# IPMC_V71V01.net
KiCad netlist of a schematic drawn in Altium Designer
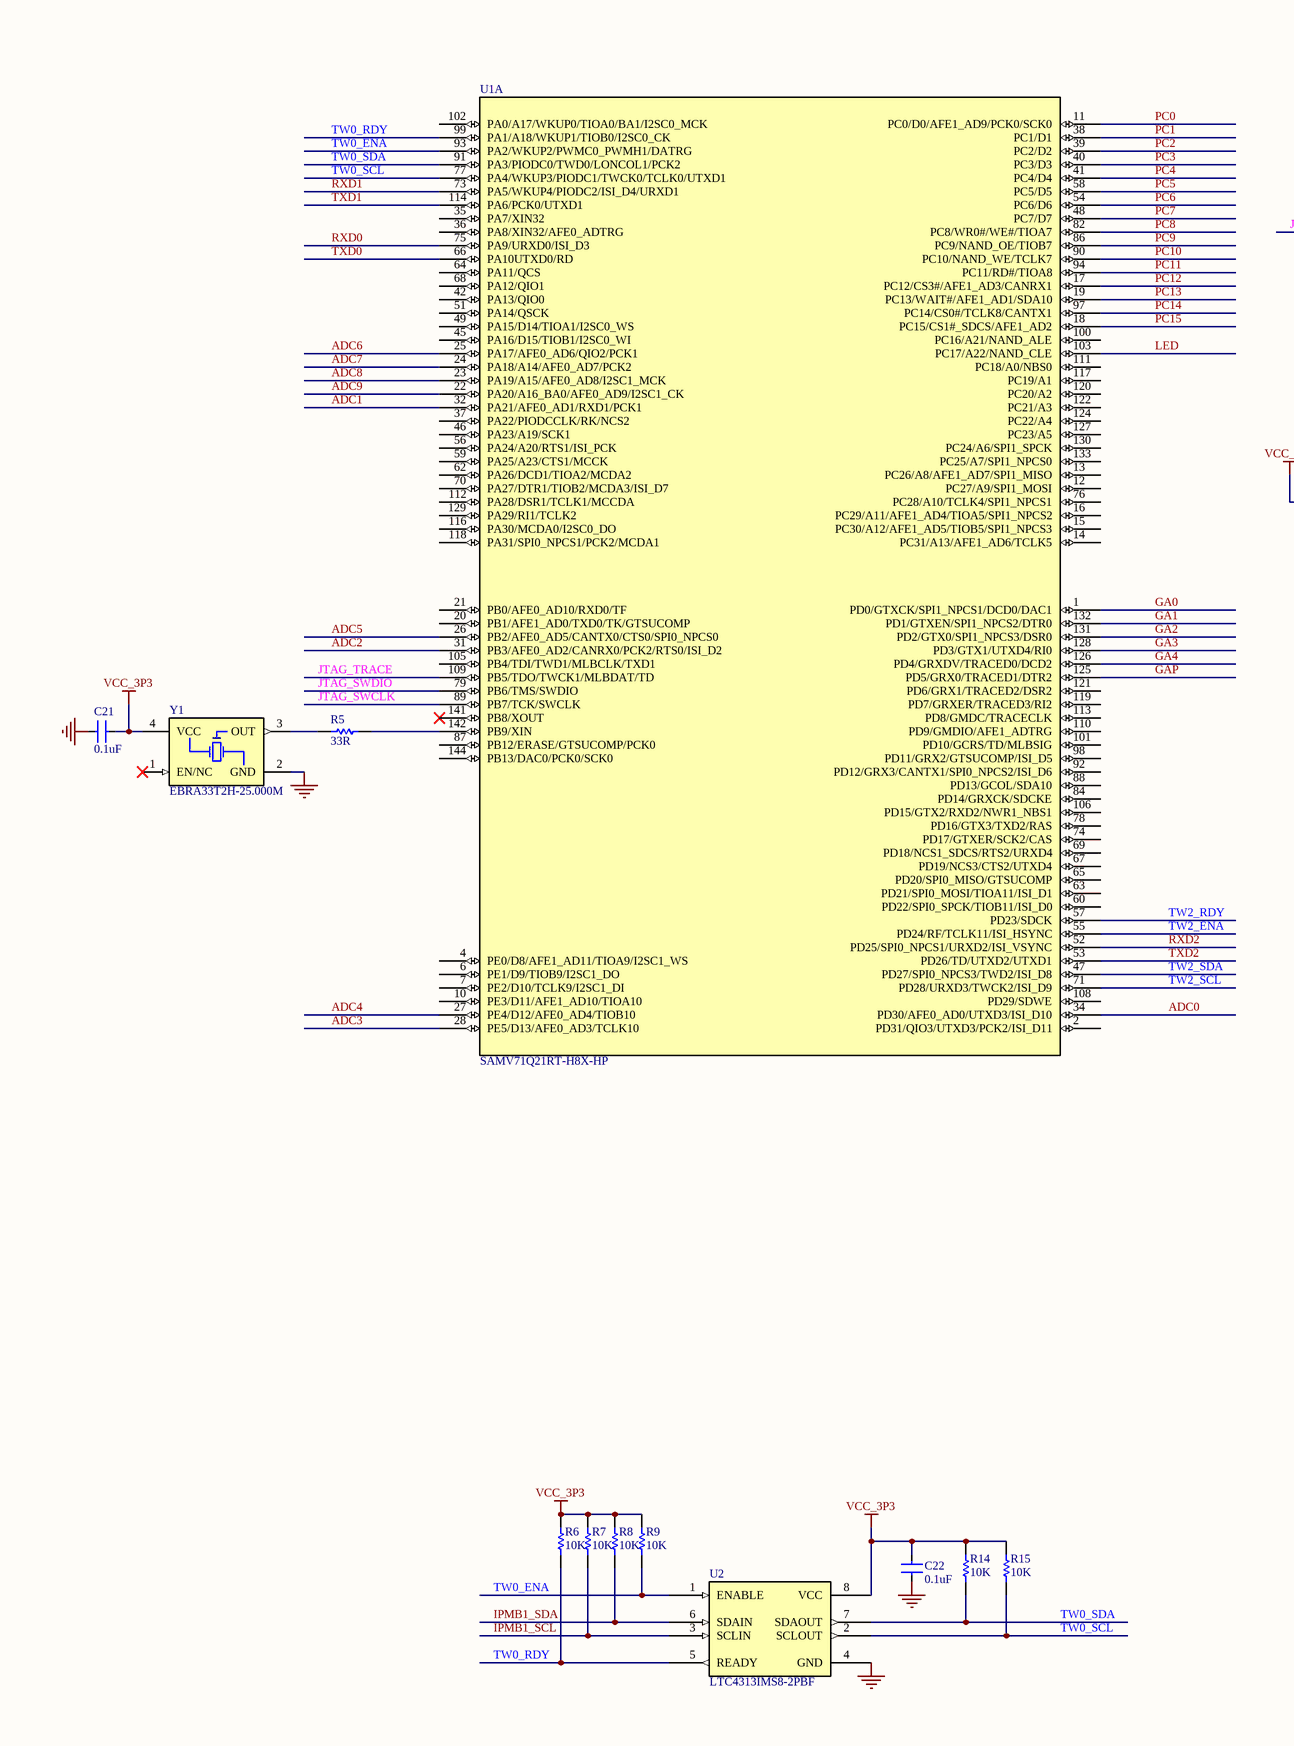
[diagram p0: IPMC_V71V01.SchDoc, left]
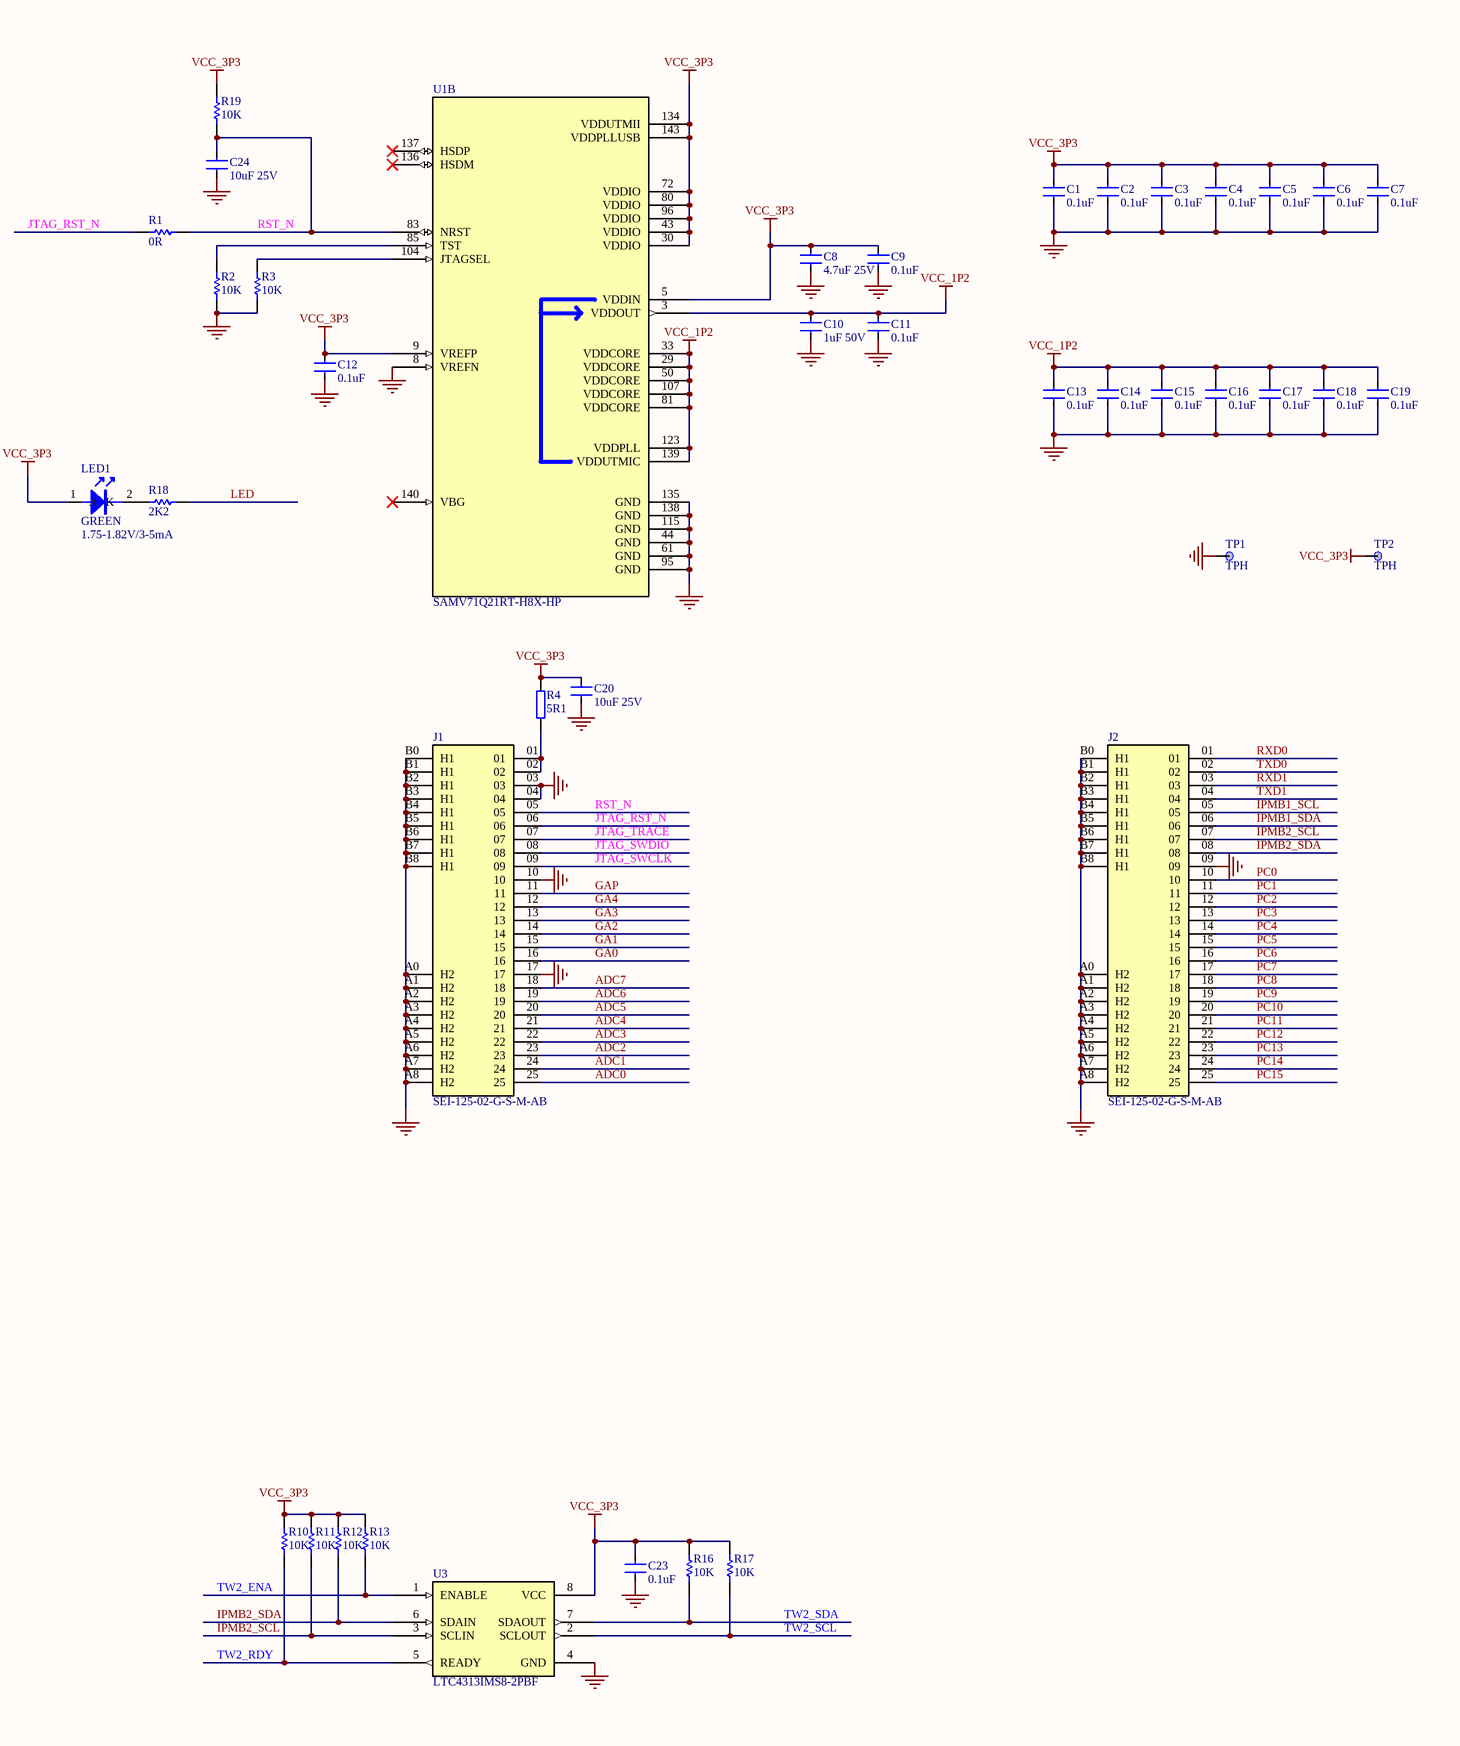
[diagram p1: IPMC_V71V01.SchDoc, right]

(export (version "E")
  (design (tool "Eeschema 10.0.6"))
  (components
    (comp (ref "C1")
      (value "0.1uF")
      (footprint "0603C")
      (description "X8L AEC-Q200")
      (fields (field (name "MANUFACTURER") "muRata") (field (name "PARTNUMBER") "GCJ188L8EL104KA07"))
      (libsource (lib "AD20_RCX") (part "CAP-0.1u-100v-0603"))
    )
    (comp (ref "C2")
      (value "0.1uF")
      (footprint "0603C")
      (description "X8L AEC-Q200")
      (fields (field (name "MANUFACTURER") "muRata") (field (name "PARTNUMBER") "GCJ188L8EL104KA07"))
      (libsource (lib "AD20_RCX") (part "CAP-0.1u-100v-0603"))
    )
    (comp (ref "C3")
      (value "0.1uF")
      (footprint "0603C")
      (description "X8L AEC-Q200")
      (fields (field (name "MANUFACTURER") "muRata") (field (name "PARTNUMBER") "GCJ188L8EL104KA07"))
      (libsource (lib "AD20_RCX") (part "CAP-0.1u-100v-0603"))
    )
    (comp (ref "C4")
      (value "0.1uF")
      (footprint "0603C")
      (description "X8L AEC-Q200")
      (fields (field (name "MANUFACTURER") "muRata") (field (name "PARTNUMBER") "GCJ188L8EL104KA07"))
      (libsource (lib "AD20_RCX") (part "CAP-0.1u-100v-0603"))
    )
    (comp (ref "C5")
      (value "0.1uF")
      (footprint "0603C")
      (description "X8L AEC-Q200")
      (fields (field (name "MANUFACTURER") "muRata") (field (name "PARTNUMBER") "GCJ188L8EL104KA07"))
      (libsource (lib "AD20_RCX") (part "CAP-0.1u-100v-0603"))
    )
    (comp (ref "C6")
      (value "0.1uF")
      (footprint "0603C")
      (description "X8L AEC-Q200")
      (fields (field (name "MANUFACTURER") "muRata") (field (name "PARTNUMBER") "GCJ188L8EL104KA07"))
      (libsource (lib "AD20_RCX") (part "CAP-0.1u-100v-0603"))
    )
    (comp (ref "C7")
      (value "0.1uF")
      (footprint "0603C")
      (description "X8L AEC-Q200")
      (fields (field (name "MANUFACTURER") "muRata") (field (name "PARTNUMBER") "GCJ188L8EL104KA07"))
      (libsource (lib "AD20_RCX") (part "CAP-0.1u-100v-0603"))
    )
    (comp (ref "C8")
      (value "4.7uF 25V")
      (footprint "0603C")
      (description "X5R AEC-Q200")
      (fields (field (name "PARTNUMBER") "GRT188R61E475KE13") (field (name "MANUFACTURER") "muRata"))
      (libsource (lib "AD20_RCX") (part "CAP-4.7u-25v-0603"))
    )
    (comp (ref "C9")
      (value "0.1uF")
      (footprint "0603C")
      (description "X8L AEC-Q200")
      (fields (field (name "MANUFACTURER") "muRata") (field (name "PARTNUMBER") "GCJ188L8EL104KA07"))
      (libsource (lib "AD20_RCX") (part "CAP-0.1u-100v-0603"))
    )
    (comp (ref "C10")
      (value "1uF 50V")
      (footprint "0603C")
      (description "X5R AEC-Q200")
      (fields (field (name "PARTNUMBER") "GRT188R61H105KE13") (field (name "MANUFACTURER") "muRata"))
      (libsource (lib "AD20_RCX") (part "CAP-1u-50v-0603"))
    )
    (comp (ref "C11")
      (value "0.1uF")
      (footprint "0603C")
      (description "X8L AEC-Q200")
      (fields (field (name "MANUFACTURER") "muRata") (field (name "PARTNUMBER") "GCJ188L8EL104KA07"))
      (libsource (lib "AD20_RCX") (part "CAP-0.1u-100v-0603"))
    )
    (comp (ref "C12")
      (value "0.1uF")
      (footprint "0603C")
      (description "X8L AEC-Q200")
      (fields (field (name "MANUFACTURER") "muRata") (field (name "PARTNUMBER") "GCJ188L8EL104KA07"))
      (libsource (lib "AD20_RCX") (part "CAP-0.1u-100v-0603"))
    )
    (comp (ref "C13")
      (value "0.1uF")
      (footprint "0603C")
      (description "X8L AEC-Q200")
      (fields (field (name "MANUFACTURER") "muRata") (field (name "PARTNUMBER") "GCJ188L8EL104KA07"))
      (libsource (lib "AD20_RCX") (part "CAP-0.1u-100v-0603"))
    )
    (comp (ref "C14")
      (value "0.1uF")
      (footprint "0603C")
      (description "X8L AEC-Q200")
      (fields (field (name "MANUFACTURER") "muRata") (field (name "PARTNUMBER") "GCJ188L8EL104KA07"))
      (libsource (lib "AD20_RCX") (part "CAP-0.1u-100v-0603"))
    )
    (comp (ref "C15")
      (value "0.1uF")
      (footprint "0603C")
      (description "X8L AEC-Q200")
      (fields (field (name "MANUFACTURER") "muRata") (field (name "PARTNUMBER") "GCJ188L8EL104KA07"))
      (libsource (lib "AD20_RCX") (part "CAP-0.1u-100v-0603"))
    )
    (comp (ref "C16")
      (value "0.1uF")
      (footprint "0603C")
      (description "X8L AEC-Q200")
      (fields (field (name "MANUFACTURER") "muRata") (field (name "PARTNUMBER") "GCJ188L8EL104KA07"))
      (libsource (lib "AD20_RCX") (part "CAP-0.1u-100v-0603"))
    )
    (comp (ref "C17")
      (value "0.1uF")
      (footprint "0603C")
      (description "X8L AEC-Q200")
      (fields (field (name "MANUFACTURER") "muRata") (field (name "PARTNUMBER") "GCJ188L8EL104KA07"))
      (libsource (lib "AD20_RCX") (part "CAP-0.1u-100v-0603"))
    )
    (comp (ref "C18")
      (value "0.1uF")
      (footprint "0603C")
      (description "X8L AEC-Q200")
      (fields (field (name "MANUFACTURER") "muRata") (field (name "PARTNUMBER") "GCJ188L8EL104KA07"))
      (libsource (lib "AD20_RCX") (part "CAP-0.1u-100v-0603"))
    )
    (comp (ref "C19")
      (value "0.1uF")
      (footprint "0603C")
      (description "X8L AEC-Q200")
      (fields (field (name "MANUFACTURER") "muRata") (field (name "PARTNUMBER") "GCJ188L8EL104KA07"))
      (libsource (lib "AD20_RCX") (part "CAP-0.1u-100v-0603"))
    )
    (comp (ref "C20")
      (value "10uF 25V")
      (footprint "0603C")
      (description "X5R AEC-Q200")
      (fields (field (name "PARTNUMBER") "GRT188R61E106ME13") (field (name "MANUFACTURER") "muRata"))
      (libsource (lib "AD20_RCX") (part "CAP-10u-25v-0603"))
    )
    (comp (ref "C21")
      (value "0.1uF")
      (footprint "0603C")
      (description "X7R AEC-Q200")
      (fields (field (name "PARTNUMBER") "GCJ188R71H104KA12") (field (name "MANUFACTURER") "muRata"))
      (libsource (lib "AD") (part "CAP-0.1u-50v-0603"))
    )
    (comp (ref "C22")
      (value "0.1uF")
      (footprint "0603C")
      (description "X7R AEC-Q200")
      (fields (field (name "PARTNUMBER") "GCJ188R71H104KA12") (field (name "MANUFACTURER") "muRata"))
      (libsource (lib "AD") (part "CAP-0.1u-50v-0603"))
    )
    (comp (ref "C23")
      (value "0.1uF")
      (footprint "0603C")
      (description "X7R AEC-Q200")
      (fields (field (name "PARTNUMBER") "GCJ188R71H104KA12") (field (name "MANUFACTURER") "muRata"))
      (libsource (lib "AD") (part "CAP-0.1u-50v-0603"))
    )
    (comp (ref "C24")
      (value "10uF 25V")
      (footprint "0603C")
      (description "X5R AEC-Q200")
      (fields (field (name "PARTNUMBER") "GRT188R61E106ME13") (field (name "MANUFACTURER") "muRata"))
      (libsource (lib "AD20_RCX") (part "CAP-10u-25v-0603"))
    )
    (comp (ref "J1")
      (value "SEI-125-02-G-S-M-AB")
      (footprint "SAMTEC_SEI-125-02-G-S-M-AB_IPMC")
      (description "25 Position Spring Compression Contact, Non-Gendered Connector Surface Mount")
      (fields (field (name "MF") "Samtec") (field (name "MP") "SEI-125-02-G-S-E-AB"))
      (libsource (lib "ChMC_V71V01_PCB_Project") (part "SEI-125-02-G-S-E-AB"))
    )
    (comp (ref "J2")
      (value "SEI-125-02-G-S-M-AB")
      (footprint "SAMTEC_SEI-125-02-G-S-M-AB_IPMC")
      (description "25 Position Spring Compression Contact, Non-Gendered Connector Surface Mount")
      (fields (field (name "MF") "Samtec") (field (name "MP") "SEI-125-02-G-S-E-AB"))
      (libsource (lib "ChMC_V71V01_PCB_Project") (part "SEI-125-02-G-S-E-AB"))
    )
    (comp (ref "LED1")
      (value "GREEN")
      (footprint "0603LED")
      (description "1.75-1.82V/3-5mA")
      (fields (field (name "PARAMETER 1") "1.75-1.82V/3-5mA"))
      (libsource (lib "AD20_RCX") (part "D-LED0603-GREEN"))
    )
    (comp (ref "R1")
      (value "0R")
      (footprint "0603R")
      (description "1%/0603")
      (fields (field (name "PARTNUMBER") "AC0603FR-070RL") (field (name "MANUFACTURER") "YAGEO"))
      (libsource (lib "AD20_RCX") (part "Res1-0R"))
    )
    (comp (ref "R2")
      (value "10K")
      (footprint "0603R")
      (description "1%/0603")
      (fields (field (name "PARTNUMBER") "AC0603FR-0710KL") (field (name "MANUFACTURER") "YAGEO"))
      (libsource (lib "AD20_RCX") (part "Res1-10K"))
    )
    (comp (ref "R3")
      (value "10K")
      (footprint "0603R")
      (description "1%/0603")
      (fields (field (name "PARTNUMBER") "AC0603FR-0710KL") (field (name "MANUFACTURER") "YAGEO"))
      (libsource (lib "AD20_RCX") (part "Res1-10K"))
    )
    (comp (ref "R4")
      (value "5R1")
      (footprint "0805R")
      (description "1%/0805")
      (fields (field (name "PARTNUMBER") "AC0805FR-075R1L") (field (name "MANUFACTURER") "YAGEO"))
      (libsource (lib "AD20_RCX") (part "Res2-5R1-0805"))
    )
    (comp (ref "R5")
      (value "33R")
      (footprint "0603R")
      (description "1%/0603")
      (fields (field (name "PARTNUMBER") "AC0603FR-0733RL") (field (name "MANUFACTURER") "YAGEO"))
      (libsource (lib "AD20_RCX") (part "Res1-33R"))
    )
    (comp (ref "R6")
      (value "10K")
      (footprint "0603R")
      (description "1%/0603")
      (fields (field (name "PARTNUMBER") "AC0603FR-0710KL") (field (name "MANUFACTURER") "YAGEO"))
      (libsource (lib "AD20_RCX") (part "Res1-10K"))
    )
    (comp (ref "R7")
      (value "10K")
      (footprint "0603R")
      (description "1%/0603")
      (fields (field (name "PARTNUMBER") "AC0603FR-0710KL") (field (name "MANUFACTURER") "YAGEO"))
      (libsource (lib "AD20_RCX") (part "Res1-10K"))
    )
    (comp (ref "R8")
      (value "10K")
      (footprint "0603R")
      (description "1%/0603")
      (fields (field (name "PARTNUMBER") "AC0603FR-0710KL") (field (name "MANUFACTURER") "YAGEO"))
      (libsource (lib "AD20_RCX") (part "Res1-10K"))
    )
    (comp (ref "R9")
      (value "10K")
      (footprint "0603R")
      (description "1%/0603")
      (fields (field (name "PARTNUMBER") "AC0603FR-0710KL") (field (name "MANUFACTURER") "YAGEO"))
      (libsource (lib "AD20_RCX") (part "Res1-10K"))
    )
    (comp (ref "R10")
      (value "10K")
      (footprint "0603R")
      (description "1%/0603")
      (fields (field (name "PARTNUMBER") "AC0603FR-0710KL") (field (name "MANUFACTURER") "YAGEO"))
      (libsource (lib "AD20_RCX") (part "Res1-10K"))
    )
    (comp (ref "R11")
      (value "10K")
      (footprint "0603R")
      (description "1%/0603")
      (fields (field (name "PARTNUMBER") "AC0603FR-0710KL") (field (name "MANUFACTURER") "YAGEO"))
      (libsource (lib "AD20_RCX") (part "Res1-10K"))
    )
    (comp (ref "R12")
      (value "10K")
      (footprint "0603R")
      (description "1%/0603")
      (fields (field (name "PARTNUMBER") "AC0603FR-0710KL") (field (name "MANUFACTURER") "YAGEO"))
      (libsource (lib "AD20_RCX") (part "Res1-10K"))
    )
    (comp (ref "R13")
      (value "10K")
      (footprint "0603R")
      (description "1%/0603")
      (fields (field (name "PARTNUMBER") "AC0603FR-0710KL") (field (name "MANUFACTURER") "YAGEO"))
      (libsource (lib "AD20_RCX") (part "Res1-10K"))
    )
    (comp (ref "R14")
      (value "10K")
      (footprint "0603R")
      (description "1%/0603")
      (fields (field (name "PARTNUMBER") "AC0603FR-0710KL") (field (name "MANUFACTURER") "YAGEO"))
      (libsource (lib "IPMCv01_PCB_Project") (part "Res1-10K"))
    )
    (comp (ref "R15")
      (value "10K")
      (footprint "0603R")
      (description "1%/0603")
      (fields (field (name "PARTNUMBER") "AC0603FR-0710KL") (field (name "MANUFACTURER") "YAGEO"))
      (libsource (lib "IPMCv01_PCB_Project") (part "Res1-10K"))
    )
    (comp (ref "R16")
      (value "10K")
      (footprint "0603R")
      (description "1%/0603")
      (fields (field (name "PARTNUMBER") "AC0603FR-0710KL") (field (name "MANUFACTURER") "YAGEO"))
      (libsource (lib "IPMCv01_PCB_Project") (part "Res1-10K"))
    )
    (comp (ref "R17")
      (value "10K")
      (footprint "0603R")
      (description "1%/0603")
      (fields (field (name "PARTNUMBER") "AC0603FR-0710KL") (field (name "MANUFACTURER") "YAGEO"))
      (libsource (lib "IPMCv01_PCB_Project") (part "Res1-10K"))
    )
    (comp (ref "R18")
      (value "2K2")
      (footprint "0603R")
      (description "1%/0603")
      (fields (field (name "PARTNUMBER") "AC0603FR-072K2L") (field (name "MANUFACTURER") "YAGEO"))
      (libsource (lib "AD20_RCX") (part "Res1-2K2"))
    )
    (comp (ref "R19")
      (value "10K")
      (footprint "0603R")
      (description "1%/0603")
      (fields (field (name "PARTNUMBER") "AC0603FR-0710KL") (field (name "MANUFACTURER") "YAGEO"))
      (libsource (lib "AD20_RCX") (part "Res1-10K"))
    )
    (comp (ref "TP1") (value "TPH") (footprint "TP") (libsource (lib "AD20_CON") (part "TPH")))
    (comp (ref "TP2") (value "TPH") (footprint "TP") (libsource (lib "AD20_CON") (part "TPH")))
    (comp (ref "U1")
      (value "SAMV71Q21RT-H8X-HP")
      (footprint "LQFP144_2SB_MCH")
      (description "No Description Available")
      (libsource (lib "AD20_IC") (part "SAMV71Q21RT-H8X-HP"))
    )
    (comp (ref "U2")
      (value "LTC4313IMS8-2PBF")
      (footprint "MSOP-8_MS_LIT")
      (description "No Description Available")
      (libsource (lib "AD20_IC") (part "LTC4313IMS8-1PBF"))
    )
    (comp (ref "U3")
      (value "LTC4313IMS8-2PBF")
      (footprint "MSOP-8_MS_LIT")
      (description "No Description Available")
      (libsource (lib "AD20_IC") (part "LTC4313IMS8-1PBF"))
    )
    (comp (ref "Y1")
      (value "EBRA33T2H-25.000M")
      (footprint "50.000M 3P3 50PPM 10PF 3.2*5.0MM")
      (description "SPXO AEC-Q200")
      (fields (field (name "MANUFACTURER") "Ecliptec") (field (name "PARTNUMBER") "EBRA23T1H-50.000M"))
      (libsource (lib "AD20_RCX") (part "XTAL3_50M_SPXO_3.2_5.0"))
    )
  )
  (nets
    (net (code "1") (name "/ADC0") (class "Default")
      (node (ref "J1") (pin "25") (pinfunction "25_25") (pintype "passive"))
      (node (ref "U1") (pin "34") (pinfunction "PD30/UTXD3/ISI_D10_34") (pintype "bidirectional"))
    )
    (net (code "2") (name "/ADC1") (class "Default")
      (node (ref "J1") (pin "24") (pinfunction "24_24") (pintype "passive"))
      (node (ref "U1") (pin "32") (pinfunction "PA21/AFE0_AD1/RXD1/PCK1_32") (pintype "bidirectional"))
    )
    (net (code "3") (name "/ADC2") (class "Default")
      (node (ref "J1") (pin "23") (pinfunction "23_23") (pintype "passive"))
      (node (ref "U1") (pin "31") (pinfunction "PB3/AFE0_AD2/CANRX0/PCK2/RTS0/ISI_D2_31") (pintype "bidirectional"))
    )
    (net (code "4") (name "/ADC3") (class "Default")
      (node (ref "J1") (pin "22") (pinfunction "22_22") (pintype "passive"))
      (node (ref "U1") (pin "28") (pinfunction "PE5/D13/AFE0_AD3/TCLK10_28") (pintype "bidirectional"))
    )
    (net (code "5") (name "/ADC4") (class "Default")
      (node (ref "J1") (pin "21") (pinfunction "21_21") (pintype "passive"))
      (node (ref "U1") (pin "27") (pinfunction "PE4/D12/AFE0_AD4/TIOB10_27") (pintype "bidirectional"))
    )
    (net (code "6") (name "/ADC5") (class "Default")
      (node (ref "J1") (pin "20") (pinfunction "20_20") (pintype "passive"))
      (node (ref "U1") (pin "26") (pinfunction "PB2/AFE0_AD5/CANTX0/CTS0/SPI0_NPCS0_26") (pintype "bidirectional"))
    )
    (net (code "7") (name "/ADC6") (class "Default")
      (node (ref "J1") (pin "19") (pinfunction "19_19") (pintype "passive"))
      (node (ref "U1") (pin "25") (pinfunction "PA17/AFE0_AD6/QIO2/PCK1_25") (pintype "bidirectional"))
    )
    (net (code "8") (name "/ADC7") (class "Default")
      (node (ref "J1") (pin "18") (pinfunction "18_18") (pintype "passive"))
      (node (ref "U1") (pin "24") (pinfunction "PA18/A14/AFE0_AD7/PCK2_24") (pintype "bidirectional"))
    )
    (net (code "9") (name "/ADC8") (class "Default")
      (node (ref "U1") (pin "23") (pinfunction "PA19/A15/AFE0_AD8/I2SC1_MCK_23") (pintype "bidirectional"))
    )
    (net (code "10") (name "/ADC9") (class "Default")
      (node (ref "U1") (pin "22") (pinfunction "PA20/A16_BA0/AFE0_AD9/I2SC1_CK_22") (pintype "bidirectional"))
    )
    (net (code "11") (name "/GA0") (class "Default")
      (node (ref "J1") (pin "16") (pinfunction "16_16") (pintype "passive"))
      (node (ref "U1") (pin "1") (pinfunction "PD0/GTXCK/SPI1_NPCS1/DCD0/DAC1_1") (pintype "bidirectional"))
    )
    (net (code "12") (name "/GA1") (class "Default")
      (node (ref "J1") (pin "15") (pinfunction "15_15") (pintype "passive"))
      (node (ref "U1") (pin "132") (pinfunction "PD1/GTXEN/SPI1_NPCS2/DTR0_132") (pintype "bidirectional"))
    )
    (net (code "13") (name "/GA2") (class "Default")
      (node (ref "J1") (pin "14") (pinfunction "14_14") (pintype "passive"))
      (node (ref "U1") (pin "131") (pinfunction "PD2/GTX0/SPI1_NPCS3/DSR0_131") (pintype "bidirectional"))
    )
    (net (code "14") (name "/GA3") (class "Default")
      (node (ref "J1") (pin "13") (pinfunction "13_13") (pintype "passive"))
      (node (ref "U1") (pin "128") (pinfunction "PD3/GTX1/UTXD4/RI0_128") (pintype "bidirectional"))
    )
    (net (code "15") (name "/GA4") (class "Default")
      (node (ref "J1") (pin "12") (pinfunction "12_12") (pintype "passive"))
      (node (ref "U1") (pin "126") (pinfunction "PD4/GRXDV/TRACED0/DCD2_126") (pintype "bidirectional"))
    )
    (net (code "16") (name "/GAP") (class "Default")
      (node (ref "J1") (pin "11") (pinfunction "11_11") (pintype "passive"))
      (node (ref "U1") (pin "125") (pinfunction "PD5/GRX0/TRACED1/DTR2_125") (pintype "bidirectional"))
    )
    (net (code "17") (name "/IPMB1_SCL") (class "Default")
      (node (ref "J2") (pin "05") (pinfunction "05_05") (pintype "passive"))
      (node (ref "R7") (pin "1") (pinfunction "1_1") (pintype "passive"))
      (node (ref "U2") (pin "3") (pinfunction "SCLIN_3") (pintype "input"))
    )
    (net (code "18") (name "/IPMB1_SDA") (class "Default")
      (node (ref "J2") (pin "06") (pinfunction "06_06") (pintype "passive"))
      (node (ref "R8") (pin "1") (pinfunction "1_1") (pintype "passive"))
      (node (ref "U2") (pin "6") (pinfunction "SDAIN_6") (pintype "input"))
    )
    (net (code "19") (name "/IPMB2_SCL") (class "Default")
      (node (ref "J2") (pin "07") (pinfunction "07_07") (pintype "passive"))
      (node (ref "R11") (pin "1") (pinfunction "1_1") (pintype "passive"))
      (node (ref "U3") (pin "3") (pinfunction "SCLIN_3") (pintype "input"))
    )
    (net (code "20") (name "/IPMB2_SDA") (class "Default")
      (node (ref "J2") (pin "08") (pinfunction "08_08") (pintype "passive"))
      (node (ref "R12") (pin "1") (pinfunction "1_1") (pintype "passive"))
      (node (ref "U3") (pin "6") (pinfunction "SDAIN_6") (pintype "input"))
    )
    (net (code "21") (name "/JTAG_RST_N") (class "Default")
      (node (ref "J1") (pin "06") (pinfunction "06_06") (pintype "passive"))
      (node (ref "R1") (pin "1") (pinfunction "1_1") (pintype "passive"))
    )
    (net (code "22") (name "/JTAG_SWCLK") (class "Default")
      (node (ref "J1") (pin "09") (pinfunction "09_09") (pintype "passive"))
      (node (ref "U1") (pin "89") (pinfunction "PB7/TCK/SWCLK_89") (pintype "bidirectional"))
    )
    (net (code "23") (name "/JTAG_SWDIO") (class "Default")
      (node (ref "J1") (pin "08") (pinfunction "08_08") (pintype "passive"))
      (node (ref "U1") (pin "79") (pinfunction "PB6/TMS/SWDIO_79") (pintype "bidirectional"))
    )
    (net (code "24") (name "/JTAG_TRACE") (class "Default")
      (node (ref "J1") (pin "07") (pinfunction "07_07") (pintype "passive"))
      (node (ref "U1") (pin "109") (pinfunction "PB5/TDO/TWCK1/MLBDAT/TD_109") (pintype "bidirectional"))
    )
    (net (code "25") (name "/LED") (class "Default")
      (node (ref "R18") (pin "2") (pinfunction "2_2") (pintype "passive"))
      (node (ref "U1") (pin "103") (pinfunction "PC17/A22/NAND_CLE_103") (pintype "bidirectional"))
    )
    (net (code "26") (name "/PC0") (class "Default")
      (node (ref "J2") (pin "10") (pinfunction "10_10") (pintype "passive"))
      (node (ref "U1") (pin "11") (pinfunction "PC0/D0/AFE1_AD9/PCK0/SCK0_11") (pintype "bidirectional"))
    )
    (net (code "27") (name "/PC1") (class "Default")
      (node (ref "J2") (pin "11") (pinfunction "11_11") (pintype "passive"))
      (node (ref "U1") (pin "38") (pinfunction "PC1/D1_38") (pintype "bidirectional"))
    )
    (net (code "28") (name "/PC2") (class "Default")
      (node (ref "J2") (pin "12") (pinfunction "12_12") (pintype "passive"))
      (node (ref "U1") (pin "39") (pinfunction "PC2/D2_39") (pintype "bidirectional"))
    )
    (net (code "29") (name "/PC3") (class "Default")
      (node (ref "J2") (pin "13") (pinfunction "13_13") (pintype "passive"))
      (node (ref "U1") (pin "40") (pinfunction "PC3/D3_40") (pintype "bidirectional"))
    )
    (net (code "30") (name "/PC4") (class "Default")
      (node (ref "J2") (pin "14") (pinfunction "14_14") (pintype "passive"))
      (node (ref "U1") (pin "41") (pinfunction "PC4/D4_41") (pintype "bidirectional"))
    )
    (net (code "31") (name "/PC5") (class "Default")
      (node (ref "J2") (pin "15") (pinfunction "15_15") (pintype "passive"))
      (node (ref "U1") (pin "58") (pinfunction "PC5/D5_58") (pintype "bidirectional"))
    )
    (net (code "32") (name "/PC6") (class "Default")
      (node (ref "J2") (pin "16") (pinfunction "16_16") (pintype "passive"))
      (node (ref "U1") (pin "54") (pinfunction "PC6/D6_54") (pintype "bidirectional"))
    )
    (net (code "33") (name "/PC7") (class "Default")
      (node (ref "J2") (pin "17") (pinfunction "17_17") (pintype "passive"))
      (node (ref "U1") (pin "48") (pinfunction "PC7/D7_48") (pintype "bidirectional"))
    )
    (net (code "34") (name "/PC8") (class "Default")
      (node (ref "J2") (pin "18") (pinfunction "18_18") (pintype "passive"))
      (node (ref "U1") (pin "82") (pinfunction "PC8/WR0#/WE#/TIOA7_82") (pintype "bidirectional"))
    )
    (net (code "35") (name "/PC9") (class "Default")
      (node (ref "J2") (pin "19") (pinfunction "19_19") (pintype "passive"))
      (node (ref "U1") (pin "86") (pinfunction "PC9/NAND_OE/TIOB7_86") (pintype "bidirectional"))
    )
    (net (code "36") (name "/PC10") (class "Default")
      (node (ref "J2") (pin "20") (pinfunction "20_20") (pintype "passive"))
      (node (ref "U1") (pin "90") (pinfunction "PC10/NAND_WE/TCLK7_90") (pintype "bidirectional"))
    )
    (net (code "37") (name "/PC11") (class "Default")
      (node (ref "J2") (pin "21") (pinfunction "21_21") (pintype "passive"))
      (node (ref "U1") (pin "94") (pinfunction "PC11/RD#/TIOA8_94") (pintype "bidirectional"))
    )
    (net (code "38") (name "/PC12") (class "Default")
      (node (ref "J2") (pin "22") (pinfunction "22_22") (pintype "passive"))
      (node (ref "U1") (pin "17") (pinfunction "PC12/CS3#/AFE1_AD3/CANRX1_17") (pintype "bidirectional"))
    )
    (net (code "39") (name "/PC13") (class "Default")
      (node (ref "J2") (pin "23") (pinfunction "23_23") (pintype "passive"))
      (node (ref "U1") (pin "19") (pinfunction "PC13/WAIT#/AFE1_AD1/SDA10_19") (pintype "bidirectional"))
    )
    (net (code "40") (name "/PC14") (class "Default")
      (node (ref "J2") (pin "24") (pinfunction "24_24") (pintype "passive"))
      (node (ref "U1") (pin "97") (pinfunction "PC14/CS0#/TCLK8/CANTX1_97") (pintype "bidirectional"))
    )
    (net (code "41") (name "/PC15") (class "Default")
      (node (ref "J2") (pin "25") (pinfunction "25_25") (pintype "passive"))
      (node (ref "U1") (pin "18") (pinfunction "PC15/CS1#_SDCS/AFE1_AD2_18") (pintype "bidirectional"))
    )
    (net (code "42") (name "/RST_N") (class "Default")
      (node (ref "C24") (pin "2") (pinfunction "2_2") (pintype "passive"))
      (node (ref "J1") (pin "05") (pinfunction "05_05") (pintype "passive"))
      (node (ref "R1") (pin "2") (pinfunction "2_2") (pintype "passive"))
      (node (ref "R19") (pin "1") (pinfunction "1_1") (pintype "passive"))
      (node (ref "U1") (pin "83") (pinfunction "NRST_83") (pintype "bidirectional"))
    )
    (net (code "43") (name "/RXD0") (class "Default")
      (node (ref "J2") (pin "01") (pinfunction "01_01") (pintype "passive"))
      (node (ref "U1") (pin "75") (pinfunction "PA9/URXD0/ISI_D3_75") (pintype "bidirectional"))
    )
    (net (code "44") (name "/RXD1") (class "Default")
      (node (ref "J2") (pin "03") (pinfunction "03_03") (pintype "passive"))
      (node (ref "U1") (pin "73") (pinfunction "PA5/WKUP4/PIODC2/ISI_D4/URXD1_73") (pintype "bidirectional"))
    )
    (net (code "45") (name "/RXD2") (class "Default")
      (node (ref "U1") (pin "52") (pinfunction "PD25/SPI0_NPCS1/URXD2/ISI_VSYNC_52") (pintype "bidirectional"))
    )
    (net (code "46") (name "/TW0_ENA") (class "Default")
      (node (ref "R9") (pin "1") (pinfunction "1_1") (pintype "passive"))
      (node (ref "U1") (pin "93") (pinfunction "PA2/WKUP2/PWMC0_PWMH1/DATRG_93") (pintype "bidirectional"))
      (node (ref "U2") (pin "1") (pinfunction "ENABLE_1") (pintype "input"))
    )
    (net (code "47") (name "/TW0_RDY") (class "Default")
      (node (ref "R6") (pin "1") (pinfunction "1_1") (pintype "passive"))
      (node (ref "U1") (pin "99") (pinfunction "PA1/A18/WKUP1/TIOB0/I2SC0_CK_99") (pintype "bidirectional"))
      (node (ref "U2") (pin "5") (pinfunction "READY_5") (pintype "output"))
    )
    (net (code "48") (name "/TW0_SCL") (class "Default")
      (node (ref "R15") (pin "1") (pinfunction "1_1") (pintype "passive"))
      (node (ref "U1") (pin "77") (pinfunction "PA4/WKUP3/PIODC1/TWCK0/TCLK0/UTXD1_77") (pintype "bidirectional"))
      (node (ref "U2") (pin "2") (pinfunction "SCLOUT_2") (pintype "output"))
    )
    (net (code "49") (name "/TW0_SDA") (class "Default")
      (node (ref "R14") (pin "1") (pinfunction "1_1") (pintype "passive"))
      (node (ref "U1") (pin "91") (pinfunction "PA3/PIODC0/TWD0/LONCOL1/PCK2_91") (pintype "bidirectional"))
      (node (ref "U2") (pin "7") (pinfunction "SDAOUT_7") (pintype "output"))
    )
    (net (code "50") (name "/TW2_ENA") (class "Default")
      (node (ref "R13") (pin "1") (pinfunction "1_1") (pintype "passive"))
      (node (ref "U1") (pin "55") (pinfunction "PD24/RF/TCLK11/ISI_HSYNC_55") (pintype "bidirectional"))
      (node (ref "U3") (pin "1") (pinfunction "ENABLE_1") (pintype "input"))
    )
    (net (code "51") (name "/TW2_RDY") (class "Default")
      (node (ref "R10") (pin "1") (pinfunction "1_1") (pintype "passive"))
      (node (ref "U1") (pin "57") (pinfunction "PD23/SDCK_57") (pintype "bidirectional"))
      (node (ref "U3") (pin "5") (pinfunction "READY_5") (pintype "output"))
    )
    (net (code "52") (name "/TW2_SCL") (class "Default")
      (node (ref "R17") (pin "1") (pinfunction "1_1") (pintype "passive"))
      (node (ref "U1") (pin "71") (pinfunction "PD28/URXD3/TWCK2/ISI_D9_71") (pintype "bidirectional"))
      (node (ref "U3") (pin "2") (pinfunction "SCLOUT_2") (pintype "output"))
    )
    (net (code "53") (name "/TW2_SDA") (class "Default")
      (node (ref "R16") (pin "1") (pinfunction "1_1") (pintype "passive"))
      (node (ref "U1") (pin "47") (pinfunction "PD27/SPI0_NPCS3/TWD2/ISI_D8_47") (pintype "bidirectional"))
      (node (ref "U3") (pin "7") (pinfunction "SDAOUT_7") (pintype "output"))
    )
    (net (code "54") (name "/TXD0") (class "Default")
      (node (ref "J2") (pin "02") (pinfunction "02_02") (pintype "passive"))
      (node (ref "U1") (pin "66") (pinfunction "PA10UTXD0/RD_66") (pintype "bidirectional"))
    )
    (net (code "55") (name "/TXD1") (class "Default")
      (node (ref "J2") (pin "04") (pinfunction "04_04") (pintype "passive"))
      (node (ref "U1") (pin "114") (pinfunction "PA6/PCK0/UTXD1_114") (pintype "bidirectional"))
    )
    (net (code "56") (name "/TXD2") (class "Default")
      (node (ref "U1") (pin "53") (pinfunction "PD26/TD/UTXD2/UTXD1_53") (pintype "bidirectional"))
    )
    (net (code "57") (name "GND") (class "Default")
      (node (ref "C1") (pin "1") (pinfunction "1_1") (pintype "passive"))
      (node (ref "C10") (pin "1") (pinfunction "1_1") (pintype "passive"))
      (node (ref "C11") (pin "1") (pinfunction "1_1") (pintype "passive"))
      (node (ref "C12") (pin "1") (pinfunction "1_1") (pintype "passive"))
      (node (ref "C13") (pin "1") (pinfunction "1_1") (pintype "passive"))
      (node (ref "C14") (pin "1") (pinfunction "1_1") (pintype "passive"))
      (node (ref "C15") (pin "1") (pinfunction "1_1") (pintype "passive"))
      (node (ref "C16") (pin "1") (pinfunction "1_1") (pintype "passive"))
      (node (ref "C17") (pin "1") (pinfunction "1_1") (pintype "passive"))
      (node (ref "C18") (pin "1") (pinfunction "1_1") (pintype "passive"))
      (node (ref "C19") (pin "1") (pinfunction "1_1") (pintype "passive"))
      (node (ref "C2") (pin "1") (pinfunction "1_1") (pintype "passive"))
      (node (ref "C20") (pin "2") (pinfunction "2_2") (pintype "passive"))
      (node (ref "C21") (pin "1") (pinfunction "1_1") (pintype "passive"))
      (node (ref "C22") (pin "2") (pinfunction "2_2") (pintype "passive"))
      (node (ref "C23") (pin "2") (pinfunction "2_2") (pintype "passive"))
      (node (ref "C24") (pin "1") (pinfunction "1_1") (pintype "passive"))
      (node (ref "C3") (pin "1") (pinfunction "1_1") (pintype "passive"))
      (node (ref "C4") (pin "1") (pinfunction "1_1") (pintype "passive"))
      (node (ref "C5") (pin "1") (pinfunction "1_1") (pintype "passive"))
      (node (ref "C6") (pin "1") (pinfunction "1_1") (pintype "passive"))
      (node (ref "C7") (pin "1") (pinfunction "1_1") (pintype "passive"))
      (node (ref "C8") (pin "1") (pinfunction "1_1") (pintype "passive"))
      (node (ref "C9") (pin "1") (pinfunction "1_1") (pintype "passive"))
      (node (ref "J1") (pin "03") (pinfunction "03_03") (pintype "passive"))
      (node (ref "J1") (pin "04") (pinfunction "04_04") (pintype "passive"))
      (node (ref "J1") (pin "10") (pinfunction "10_10") (pintype "passive"))
      (node (ref "J1") (pin "17") (pinfunction "17_17") (pintype "passive"))
      (node (ref "J1") (pin "A0") (pinfunction "H2_A0") (pintype "passive"))
      (node (ref "J1") (pin "A1") (pinfunction "H2_A1") (pintype "passive"))
      (node (ref "J1") (pin "A2") (pinfunction "H2_A2") (pintype "passive"))
      (node (ref "J1") (pin "A3") (pinfunction "H2_A3") (pintype "passive"))
      (node (ref "J1") (pin "A4") (pinfunction "H2_A4") (pintype "passive"))
      (node (ref "J1") (pin "A5") (pinfunction "H2_A5") (pintype "passive"))
      (node (ref "J1") (pin "A6") (pinfunction "H2_A6") (pintype "passive"))
      (node (ref "J1") (pin "A7") (pinfunction "H2_A7") (pintype "passive"))
      (node (ref "J1") (pin "A8") (pinfunction "H2_A8") (pintype "passive"))
      (node (ref "J1") (pin "B0") (pinfunction "H1_B0") (pintype "passive"))
      (node (ref "J1") (pin "B1") (pinfunction "H1_B1") (pintype "passive"))
      (node (ref "J1") (pin "B2") (pinfunction "H1_B2") (pintype "passive"))
      (node (ref "J1") (pin "B3") (pinfunction "H1_B3") (pintype "passive"))
      (node (ref "J1") (pin "B4") (pinfunction "H1_B4") (pintype "passive"))
      (node (ref "J1") (pin "B5") (pinfunction "H1_B5") (pintype "passive"))
      (node (ref "J1") (pin "B6") (pinfunction "H1_B6") (pintype "passive"))
      (node (ref "J1") (pin "B7") (pinfunction "H1_B7") (pintype "passive"))
      (node (ref "J1") (pin "B8") (pinfunction "H1_B8") (pintype "passive"))
      (node (ref "J2") (pin "09") (pinfunction "09_09") (pintype "passive"))
      (node (ref "J2") (pin "A0") (pinfunction "H2_A0") (pintype "passive"))
      (node (ref "J2") (pin "A1") (pinfunction "H2_A1") (pintype "passive"))
      (node (ref "J2") (pin "A2") (pinfunction "H2_A2") (pintype "passive"))
      (node (ref "J2") (pin "A3") (pinfunction "H2_A3") (pintype "passive"))
      (node (ref "J2") (pin "A4") (pinfunction "H2_A4") (pintype "passive"))
      (node (ref "J2") (pin "A5") (pinfunction "H2_A5") (pintype "passive"))
      (node (ref "J2") (pin "A6") (pinfunction "H2_A6") (pintype "passive"))
      (node (ref "J2") (pin "A7") (pinfunction "H2_A7") (pintype "passive"))
      (node (ref "J2") (pin "A8") (pinfunction "H2_A8") (pintype "passive"))
      (node (ref "J2") (pin "B0") (pinfunction "H1_B0") (pintype "passive"))
      (node (ref "J2") (pin "B1") (pinfunction "H1_B1") (pintype "passive"))
      (node (ref "J2") (pin "B2") (pinfunction "H1_B2") (pintype "passive"))
      (node (ref "J2") (pin "B3") (pinfunction "H1_B3") (pintype "passive"))
      (node (ref "J2") (pin "B4") (pinfunction "H1_B4") (pintype "passive"))
      (node (ref "J2") (pin "B5") (pinfunction "H1_B5") (pintype "passive"))
      (node (ref "J2") (pin "B6") (pinfunction "H1_B6") (pintype "passive"))
      (node (ref "J2") (pin "B7") (pinfunction "H1_B7") (pintype "passive"))
      (node (ref "J2") (pin "B8") (pinfunction "H1_B8") (pintype "passive"))
      (node (ref "R2") (pin "1") (pinfunction "1_1") (pintype "passive"))
      (node (ref "R3") (pin "1") (pinfunction "1_1") (pintype "passive"))
      (node (ref "TP1") (pin "1") (pinfunction "1_1") (pintype "passive"))
      (node (ref "U1") (pin "115") (pinfunction "GND_115") (pintype "power_in"))
      (node (ref "U1") (pin "135") (pinfunction "GND_135") (pintype "power_in"))
      (node (ref "U1") (pin "138") (pinfunction "GND_138") (pintype "power_in"))
      (node (ref "U1") (pin "44") (pinfunction "GND_44") (pintype "power_in"))
      (node (ref "U1") (pin "61") (pinfunction "GND_61") (pintype "power_in"))
      (node (ref "U1") (pin "8") (pinfunction "VREFN_8") (pintype "input"))
      (node (ref "U1") (pin "95") (pinfunction "GND_95") (pintype "power_in"))
      (node (ref "U2") (pin "4") (pinfunction "GND_4") (pintype "power_in"))
      (node (ref "U3") (pin "4") (pinfunction "GND_4") (pintype "power_in"))
      (node (ref "Y1") (pin "2") (pinfunction "GND_2") (pintype "power_in"))
    )
    (net (code "58") (name "Net-(J1-Pad01)") (class "Default")
      (node (ref "J1") (pin "01") (pinfunction "01_01") (pintype "passive"))
      (node (ref "J1") (pin "02") (pinfunction "02_02") (pintype "passive"))
      (node (ref "R4") (pin "1") (pintype "passive"))
    )
    (net (code "59") (name "Net-(LED1-K)") (class "Default")
      (node (ref "LED1") (pin "2") (pinfunction "K_2") (pintype "passive"))
      (node (ref "R18") (pin "1") (pinfunction "1_1") (pintype "passive"))
    )
    (net (code "60") (name "Net-(U1A-PB9{slash}XIN)") (class "Default")
      (node (ref "R5") (pin "2") (pinfunction "2_2") (pintype "passive"))
      (node (ref "U1") (pin "142") (pinfunction "PB9/XIN_142") (pintype "bidirectional"))
    )
    (net (code "61") (name "Net-(U1B-JTAGSEL)") (class "Default")
      (node (ref "R3") (pin "2") (pinfunction "2_2") (pintype "passive"))
      (node (ref "U1") (pin "104") (pinfunction "JTAGSEL_104") (pintype "input"))
    )
    (net (code "62") (name "Net-(U1B-TST)") (class "Default")
      (node (ref "R2") (pin "2") (pinfunction "2_2") (pintype "passive"))
      (node (ref "U1") (pin "85") (pinfunction "TST_85") (pintype "input"))
    )
    (net (code "63") (name "Net-(Y1-OUT)") (class "Default")
      (node (ref "R5") (pin "1") (pinfunction "1_1") (pintype "passive"))
      (node (ref "Y1") (pin "3") (pinfunction "OUT_3") (pintype "output"))
    )
    (net (code "64") (name "VCC_1P2") (class "Default")
      (node (ref "C10") (pin "2") (pinfunction "2_2") (pintype "passive"))
      (node (ref "C11") (pin "2") (pinfunction "2_2") (pintype "passive"))
      (node (ref "C13") (pin "2") (pinfunction "2_2") (pintype "passive"))
      (node (ref "C14") (pin "2") (pinfunction "2_2") (pintype "passive"))
      (node (ref "C15") (pin "2") (pinfunction "2_2") (pintype "passive"))
      (node (ref "C16") (pin "2") (pinfunction "2_2") (pintype "passive"))
      (node (ref "C17") (pin "2") (pinfunction "2_2") (pintype "passive"))
      (node (ref "C18") (pin "2") (pinfunction "2_2") (pintype "passive"))
      (node (ref "C19") (pin "2") (pinfunction "2_2") (pintype "passive"))
      (node (ref "U1") (pin "107") (pinfunction "VDDCORE_107") (pintype "power_in"))
      (node (ref "U1") (pin "123") (pinfunction "VDDPLL_123") (pintype "power_in"))
      (node (ref "U1") (pin "139") (pinfunction "VDDUTMIC_139") (pintype "power_in"))
      (node (ref "U1") (pin "29") (pinfunction "VDDCORE_29") (pintype "power_in"))
      (node (ref "U1") (pin "3") (pinfunction "VDDOUT_3") (pintype "output"))
      (node (ref "U1") (pin "33") (pinfunction "VDDCORE_33") (pintype "power_in"))
      (node (ref "U1") (pin "50") (pinfunction "VDDCORE_50") (pintype "power_in"))
      (node (ref "U1") (pin "81") (pinfunction "VDDCORE_81") (pintype "power_in"))
    )
    (net (code "65") (name "VCC_3P3") (class "Default")
      (node (ref "C1") (pin "2") (pinfunction "2_2") (pintype "passive"))
      (node (ref "C12") (pin "2") (pinfunction "2_2") (pintype "passive"))
      (node (ref "C2") (pin "2") (pinfunction "2_2") (pintype "passive"))
      (node (ref "C20") (pin "1") (pinfunction "1_1") (pintype "passive"))
      (node (ref "C21") (pin "2") (pinfunction "2_2") (pintype "passive"))
      (node (ref "C22") (pin "1") (pinfunction "1_1") (pintype "passive"))
      (node (ref "C23") (pin "1") (pinfunction "1_1") (pintype "passive"))
      (node (ref "C3") (pin "2") (pinfunction "2_2") (pintype "passive"))
      (node (ref "C4") (pin "2") (pinfunction "2_2") (pintype "passive"))
      (node (ref "C5") (pin "2") (pinfunction "2_2") (pintype "passive"))
      (node (ref "C6") (pin "2") (pinfunction "2_2") (pintype "passive"))
      (node (ref "C7") (pin "2") (pinfunction "2_2") (pintype "passive"))
      (node (ref "C8") (pin "2") (pinfunction "2_2") (pintype "passive"))
      (node (ref "C9") (pin "2") (pinfunction "2_2") (pintype "passive"))
      (node (ref "LED1") (pin "1") (pinfunction "A_1") (pintype "passive"))
      (node (ref "R10") (pin "2") (pinfunction "2_2") (pintype "passive"))
      (node (ref "R11") (pin "2") (pinfunction "2_2") (pintype "passive"))
      (node (ref "R12") (pin "2") (pinfunction "2_2") (pintype "passive"))
      (node (ref "R13") (pin "2") (pinfunction "2_2") (pintype "passive"))
      (node (ref "R14") (pin "2") (pinfunction "2_2") (pintype "passive"))
      (node (ref "R15") (pin "2") (pinfunction "2_2") (pintype "passive"))
      (node (ref "R16") (pin "2") (pinfunction "2_2") (pintype "passive"))
      (node (ref "R17") (pin "2") (pinfunction "2_2") (pintype "passive"))
      (node (ref "R19") (pin "2") (pinfunction "2_2") (pintype "passive"))
      (node (ref "R4") (pin "2") (pintype "passive"))
      (node (ref "R6") (pin "2") (pinfunction "2_2") (pintype "passive"))
      (node (ref "R7") (pin "2") (pinfunction "2_2") (pintype "passive"))
      (node (ref "R8") (pin "2") (pinfunction "2_2") (pintype "passive"))
      (node (ref "R9") (pin "2") (pinfunction "2_2") (pintype "passive"))
      (node (ref "TP2") (pin "1") (pinfunction "1_1") (pintype "passive"))
      (node (ref "U1") (pin "134") (pinfunction "VDDUTMII_134") (pintype "power_in"))
      (node (ref "U1") (pin "143") (pinfunction "VDDPLLUSB_143") (pintype "power_in"))
      (node (ref "U1") (pin "30") (pinfunction "VDDIO_30") (pintype "power_in"))
      (node (ref "U1") (pin "43") (pinfunction "VDDIO_43") (pintype "power_in"))
      (node (ref "U1") (pin "5") (pinfunction "VDDIN_5") (pintype "power_in"))
      (node (ref "U1") (pin "72") (pinfunction "VDDIO_72") (pintype "power_in"))
      (node (ref "U1") (pin "80") (pinfunction "VDDIO_80") (pintype "power_in"))
      (node (ref "U1") (pin "9") (pinfunction "VREFP_9") (pintype "input"))
      (node (ref "U1") (pin "96") (pinfunction "VDDIO_96") (pintype "power_in"))
      (node (ref "U2") (pin "8") (pinfunction "VCC_8") (pintype "power_in"))
      (node (ref "U3") (pin "8") (pinfunction "VCC_8") (pintype "power_in"))
      (node (ref "Y1") (pin "4") (pinfunction "VCC_4") (pintype "power_in"))
    )
    (net (code "66") (name "unconnected-(U1A-PA0{slash}A17{slash}WKUP0{slash}TIOA0{slash}BA1{slash}I2SC0_MCK-Pad102)") (class "Default")
      (node (ref "U1") (pin "102") (pinfunction "PA0/A17/WKUP0/TIOA0/BA1/I2SC0_MCK_102") (pintype "bidirectional"))
    )
    (net (code "67") (name "unconnected-(U1A-PA7{slash}XIN32-Pad35)") (class "Default")
      (node (ref "U1") (pin "35") (pinfunction "PA7/XIN32_35") (pintype "bidirectional"))
    )
    (net (code "68") (name "unconnected-(U1A-PA8{slash}XIN32{slash}AFE0_ADTRG-Pad36)") (class "Default")
      (node (ref "U1") (pin "36") (pinfunction "PA8/XIN32/AFE0_ADTRG_36") (pintype "bidirectional"))
    )
    (net (code "69") (name "unconnected-(U1A-PA11{slash}QCS-Pad64)") (class "Default")
      (node (ref "U1") (pin "64") (pinfunction "PA11/QCS_64") (pintype "bidirectional"))
    )
    (net (code "70") (name "unconnected-(U1A-PA12{slash}QIO1-Pad68)") (class "Default")
      (node (ref "U1") (pin "68") (pinfunction "PA12/QIO1_68") (pintype "bidirectional"))
    )
    (net (code "71") (name "unconnected-(U1A-PA13{slash}QIO0-Pad42)") (class "Default")
      (node (ref "U1") (pin "42") (pinfunction "PA13/QIO0_42") (pintype "bidirectional"))
    )
    (net (code "72") (name "unconnected-(U1A-PA14{slash}QSCK-Pad51)") (class "Default")
      (node (ref "U1") (pin "51") (pinfunction "PA14/QSCK_51") (pintype "bidirectional"))
    )
    (net (code "73") (name "unconnected-(U1A-PA15{slash}D14{slash}TIOA1{slash}I2SC0_WS-Pad49)") (class "Default")
      (node (ref "U1") (pin "49") (pinfunction "PA15/D14/TIOA1/I2SC0_WS_49") (pintype "bidirectional"))
    )
    (net (code "74") (name "unconnected-(U1A-PA16{slash}D15{slash}TIOB1{slash}I2SC0_WI-Pad45)") (class "Default")
      (node (ref "U1") (pin "45") (pinfunction "PA16/D15/TIOB1/I2SC0_WI_45") (pintype "bidirectional"))
    )
    (net (code "75") (name "unconnected-(U1A-PA22{slash}PIODCCLK{slash}RK{slash}NCS2-Pad37)") (class "Default")
      (node (ref "U1") (pin "37") (pinfunction "PA22/PIODCCLK/RK/NCS2_37") (pintype "bidirectional"))
    )
    (net (code "76") (name "unconnected-(U1A-PA23{slash}A19{slash}SCK1-Pad46)") (class "Default")
      (node (ref "U1") (pin "46") (pinfunction "PA23/A19/SCK1_46") (pintype "bidirectional"))
    )
    (net (code "77") (name "unconnected-(U1A-PA24{slash}A20{slash}RTS1{slash}ISI_PCK-Pad56)") (class "Default")
      (node (ref "U1") (pin "56") (pinfunction "PA24/A20/RTS1/ISI_PCK_56") (pintype "bidirectional"))
    )
    (net (code "78") (name "unconnected-(U1A-PA25{slash}A23{slash}CTS1{slash}MCCK-Pad59)") (class "Default")
      (node (ref "U1") (pin "59") (pinfunction "PA25/A23/CTS1/MCCK_59") (pintype "bidirectional"))
    )
    (net (code "79") (name "unconnected-(U1A-PA26{slash}DCD1{slash}TIOA2{slash}MCDA2-Pad62)") (class "Default")
      (node (ref "U1") (pin "62") (pinfunction "PA26/DCD1/TIOA2/MCDA2_62") (pintype "bidirectional"))
    )
    (net (code "80") (name "unconnected-(U1A-PA27{slash}DTR1{slash}TIOB2{slash}MCDA3{slash}ISI_D7-Pad70)") (class "Default")
      (node (ref "U1") (pin "70") (pinfunction "PA27/DTR1/TIOB2/MCDA3/ISI_D7_70") (pintype "bidirectional"))
    )
    (net (code "81") (name "unconnected-(U1A-PA28{slash}DSR1{slash}TCLK1{slash}MCCDA-Pad112)") (class "Default")
      (node (ref "U1") (pin "112") (pinfunction "PA28/DSR1/TCLK1/MCCDA_112") (pintype "bidirectional"))
    )
    (net (code "82") (name "unconnected-(U1A-PA29{slash}RI1{slash}TCLK2-Pad129)") (class "Default")
      (node (ref "U1") (pin "129") (pinfunction "PA29/RI1/TCLK2_129") (pintype "bidirectional"))
    )
    (net (code "83") (name "unconnected-(U1A-PA30{slash}MCDA0{slash}I2SC0_DO-Pad116)") (class "Default")
      (node (ref "U1") (pin "116") (pinfunction "PA30/MCDA0/I2SC0_DO_116") (pintype "bidirectional"))
    )
    (net (code "84") (name "unconnected-(U1A-PA31{slash}SPI0_NPCS1{slash}PCK2{slash}MCDA1-Pad118)") (class "Default")
      (node (ref "U1") (pin "118") (pinfunction "PA31/SPI0_NPCS1/PCK2/MCDA1_118") (pintype "bidirectional"))
    )
    (net (code "85") (name "unconnected-(U1A-PB0{slash}AFE0_AD10{slash}RXD0{slash}TF-Pad21)") (class "Default")
      (node (ref "U1") (pin "21") (pinfunction "PB0/AFE0_AD10/RXD0/TF_21") (pintype "bidirectional"))
    )
    (net (code "86") (name "unconnected-(U1A-PB1{slash}AFE1_AD0{slash}TXD0{slash}TK{slash}GTSUCOMP-Pad20)") (class "Default")
      (node (ref "U1") (pin "20") (pinfunction "PB1/AFE1_AD0/TXD0/TK/GTSUCOMP_20") (pintype "bidirectional"))
    )
    (net (code "87") (name "unconnected-(U1A-PB4{slash}TDI{slash}TWD1{slash}MLBCLK{slash}TXD1-Pad105)") (class "Default")
      (node (ref "U1") (pin "105") (pinfunction "PB4/TDI/TWD1/MLBCLK/TXD1_105") (pintype "bidirectional"))
    )
    (net (code "88") (name "unconnected-(U1A-PB8{slash}XOUT-Pad141)") (class "Default")
      (node (ref "U1") (pin "141") (pinfunction "PB8/XOUT_141") (pintype "bidirectional+no_connect"))
    )
    (net (code "89") (name "unconnected-(U1A-PB12{slash}ERASE{slash}GTSUCOMP{slash}PCK0-Pad87)") (class "Default")
      (node (ref "U1") (pin "87") (pinfunction "PB12/ERASE/GTSUCOMP/PCK0_87") (pintype "bidirectional"))
    )
    (net (code "90") (name "unconnected-(U1A-PB13{slash}DAC0{slash}PCK0{slash}SCK0-Pad144)") (class "Default")
      (node (ref "U1") (pin "144") (pinfunction "PB13/DAC0/PCK0/SCK0_144") (pintype "bidirectional"))
    )
    (net (code "91") (name "unconnected-(U1A-PC16{slash}A21{slash}NAND_ALE-Pad100)") (class "Default")
      (node (ref "U1") (pin "100") (pinfunction "PC16/A21/NAND_ALE_100") (pintype "bidirectional"))
    )
    (net (code "92") (name "unconnected-(U1A-PC18{slash}A0{slash}NBS0-Pad111)") (class "Default")
      (node (ref "U1") (pin "111") (pinfunction "PC18/A0/NBS0_111") (pintype "bidirectional"))
    )
    (net (code "93") (name "unconnected-(U1A-PC19{slash}A1-Pad117)") (class "Default")
      (node (ref "U1") (pin "117") (pinfunction "PC19/A1_117") (pintype "bidirectional"))
    )
    (net (code "94") (name "unconnected-(U1A-PC20{slash}A2-Pad120)") (class "Default")
      (node (ref "U1") (pin "120") (pinfunction "PC20/A2_120") (pintype "bidirectional"))
    )
    (net (code "95") (name "unconnected-(U1A-PC21{slash}A3-Pad122)") (class "Default")
      (node (ref "U1") (pin "122") (pinfunction "PC21/A3_122") (pintype "bidirectional"))
    )
    (net (code "96") (name "unconnected-(U1A-PC22{slash}A4-Pad124)") (class "Default")
      (node (ref "U1") (pin "124") (pinfunction "PC22/A4_124") (pintype "bidirectional"))
    )
    (net (code "97") (name "unconnected-(U1A-PC23{slash}A5-Pad127)") (class "Default")
      (node (ref "U1") (pin "127") (pinfunction "PC23/A5_127") (pintype "bidirectional"))
    )
    (net (code "98") (name "unconnected-(U1A-PC24{slash}A6{slash}SPI1_SPCK-Pad130)") (class "Default")
      (node (ref "U1") (pin "130") (pinfunction "PC24/A6/SPI1_SPCK_130") (pintype "bidirectional"))
    )
    (net (code "99") (name "unconnected-(U1A-PC25{slash}A7{slash}SPI1_NPCS0-Pad133)") (class "Default")
      (node (ref "U1") (pin "133") (pinfunction "PC25/A7/SPI1_NPCS0_133") (pintype "bidirectional"))
    )
    (net (code "100") (name "unconnected-(U1A-PC26{slash}A8{slash}AFE1_AD7{slash}SPI1_MISO-Pad13)") (class "Default")
      (node (ref "U1") (pin "13") (pinfunction "PC26/A8/AFE1_AD7/SPI1_MISO_13") (pintype "bidirectional"))
    )
    (net (code "101") (name "unconnected-(U1A-PC27{slash}A9{slash}SPI1_MOSI-Pad12)") (class "Default")
      (node (ref "U1") (pin "12") (pinfunction "PC27/A9/SPI1_MOSI_12") (pintype "bidirectional"))
    )
    (net (code "102") (name "unconnected-(U1A-PC28{slash}A10{slash}TCLK4{slash}SPI1_NPCS1-Pad76)") (class "Default")
      (node (ref "U1") (pin "76") (pinfunction "PC28/A10/TCLK4/SPI1_NPCS1_76") (pintype "bidirectional"))
    )
    (net (code "103") (name "unconnected-(U1A-PC29{slash}A11{slash}AFE1_AD4{slash}TIOA5{slash}SPI1_NPCS2-Pad16)") (class "Default")
      (node (ref "U1") (pin "16") (pinfunction "PC29/A11/AFE1_AD4/TIOA5/SPI1_NPCS2_16") (pintype "bidirectional"))
    )
    (net (code "104") (name "unconnected-(U1A-PC30{slash}A12{slash}AFE1_AD5{slash}TIOB5{slash}SPI1_NPCS3-Pad15)") (class "Default")
      (node (ref "U1") (pin "15") (pinfunction "PC30/A12/AFE1_AD5/TIOB5/SPI1_NPCS3_15") (pintype "bidirectional"))
    )
    (net (code "105") (name "unconnected-(U1A-PC31{slash}A13{slash}AFE1_AD6{slash}TCLK5-Pad14)") (class "Default")
      (node (ref "U1") (pin "14") (pinfunction "PC31/A13/AFE1_AD6/TCLK5_14") (pintype "bidirectional"))
    )
    (net (code "106") (name "unconnected-(U1A-PD6{slash}GRX1{slash}TRACED2{slash}DSR2-Pad121)") (class "Default")
      (node (ref "U1") (pin "121") (pinfunction "PD6/GRX1/TRACED2/DSR2_121") (pintype "bidirectional"))
    )
    (net (code "107") (name "unconnected-(U1A-PD7{slash}GRXER{slash}TRACED3{slash}RI2-Pad119)") (class "Default")
      (node (ref "U1") (pin "119") (pinfunction "PD7/GRXER/TRACED3/RI2_119") (pintype "bidirectional"))
    )
    (net (code "108") (name "unconnected-(U1A-PD8{slash}GMDC{slash}TRACECLK-Pad113)") (class "Default")
      (node (ref "U1") (pin "113") (pinfunction "PD8/GMDC/TRACECLK_113") (pintype "bidirectional"))
    )
    (net (code "109") (name "unconnected-(U1A-PD9{slash}GMDIO{slash}AFE1_ADTRG-Pad110)") (class "Default")
      (node (ref "U1") (pin "110") (pinfunction "PD9/GMDIO/AFE1_ADTRG_110") (pintype "bidirectional"))
    )
    (net (code "110") (name "unconnected-(U1A-PD10{slash}GCRS{slash}TD{slash}MLBSIG-Pad101)") (class "Default")
      (node (ref "U1") (pin "101") (pinfunction "PD10/GCRS/TD/MLBSIG_101") (pintype "bidirectional"))
    )
    (net (code "111") (name "unconnected-(U1A-PD11{slash}GRX2{slash}GTSUCOMP{slash}ISI_D5-Pad98)") (class "Default")
      (node (ref "U1") (pin "98") (pinfunction "PD11/GRX2/GTSUCOMP/ISI_D5_98") (pintype "bidirectional"))
    )
    (net (code "112") (name "unconnected-(U1A-PD12{slash}GRX3{slash}CANTX1{slash}SPI0_NPCS2{slash}ISI_D6-Pad92)") (class "Default")
      (node (ref "U1") (pin "92") (pinfunction "PD12/GRX3/CANTX1/SPI0_NPCS2/ISI_D6_92") (pintype "bidirectional"))
    )
    (net (code "113") (name "unconnected-(U1A-PD13{slash}GCOL{slash}SDA10-Pad88)") (class "Default")
      (node (ref "U1") (pin "88") (pinfunction "PD13/GCOL/SDA10_88") (pintype "bidirectional"))
    )
    (net (code "114") (name "unconnected-(U1A-PD14{slash}GRXCK{slash}SDCKE-Pad84)") (class "Default")
      (node (ref "U1") (pin "84") (pinfunction "PD14/GRXCK/SDCKE_84") (pintype "bidirectional"))
    )
    (net (code "115") (name "unconnected-(U1A-PD15{slash}GTX2{slash}RXD2{slash}NWR1_NBS1-Pad106)") (class "Default")
      (node (ref "U1") (pin "106") (pinfunction "PD15/GTX2/RXD2/NWR1_NBS1_106") (pintype "bidirectional"))
    )
    (net (code "116") (name "unconnected-(U1A-PD16{slash}GTX3{slash}TXD2{slash}RAS-Pad78)") (class "Default")
      (node (ref "U1") (pin "78") (pinfunction "PD16/GTX3/TXD2/RAS_78") (pintype "bidirectional"))
    )
    (net (code "117") (name "unconnected-(U1A-PD17{slash}GTXER{slash}SCK2{slash}CAS-Pad74)") (class "Default")
      (node (ref "U1") (pin "74") (pinfunction "PD17/GTXER/SCK2/CAS_74") (pintype "bidirectional"))
    )
    (net (code "118") (name "unconnected-(U1A-PD18{slash}NCS1_SDCS{slash}RTS2{slash}URXD4-Pad69)") (class "Default")
      (node (ref "U1") (pin "69") (pinfunction "PD18/NCS1_SDCS/RTS2/URXD4_69") (pintype "bidirectional"))
    )
    (net (code "119") (name "unconnected-(U1A-PD19{slash}NCS3{slash}CTS2{slash}UTXD4-Pad67)") (class "Default")
      (node (ref "U1") (pin "67") (pinfunction "PD19/NCS3/CTS2/UTXD4_67") (pintype "bidirectional"))
    )
    (net (code "120") (name "unconnected-(U1A-PD20{slash}SPI0_MISO{slash}GTSUCOMP-Pad65)") (class "Default")
      (node (ref "U1") (pin "65") (pinfunction "PD20/SPI0_MISO/GTSUCOMP_65") (pintype "bidirectional"))
    )
    (net (code "121") (name "unconnected-(U1A-PD21{slash}SPI0_MOSI{slash}TIOA11{slash}ISI_D1-Pad63)") (class "Default")
      (node (ref "U1") (pin "63") (pinfunction "PD21/SPI0_MOSI/TIOA11/ISI_D1_63") (pintype "bidirectional"))
    )
    (net (code "122") (name "unconnected-(U1A-PD22{slash}SPI0_SPCK{slash}TIOB11{slash}ISI_D0-Pad60)") (class "Default")
      (node (ref "U1") (pin "60") (pinfunction "PD22/SPI0_SPCK/TIOB11/ISI_D0_60") (pintype "bidirectional"))
    )
    (net (code "123") (name "unconnected-(U1A-PD29{slash}SDWE-Pad108)") (class "Default")
      (node (ref "U1") (pin "108") (pinfunction "PD29/SDWE_108") (pintype "bidirectional"))
    )
    (net (code "124") (name "unconnected-(U1A-PD31{slash}QIO3{slash}UTXD3{slash}PCK2{slash}ISI_D11-Pad2)") (class "Default")
      (node (ref "U1") (pin "2") (pinfunction "PD31/QIO3/UTXD3/PCK2/ISI_D11_2") (pintype "bidirectional"))
    )
    (net (code "125") (name "unconnected-(U1A-PE0{slash}D8{slash}AFE1_AD11{slash}TIOA9{slash}I2SC1_WS-Pad4)") (class "Default")
      (node (ref "U1") (pin "4") (pinfunction "PE0/D8/AFE1_AD11/TIOA9/I2SC1_WS_4") (pintype "bidirectional"))
    )
    (net (code "126") (name "unconnected-(U1A-PE1{slash}D9{slash}TIOB9{slash}I2SC1_DO-Pad6)") (class "Default")
      (node (ref "U1") (pin "6") (pinfunction "PE1/D9/TIOB9/I2SC1_DO_6") (pintype "bidirectional"))
    )
    (net (code "127") (name "unconnected-(U1A-PE2{slash}D10{slash}TCLK9{slash}I2SC1_DI-Pad7)") (class "Default")
      (node (ref "U1") (pin "7") (pinfunction "PE2/D10/TCLK9/I2SC1_DI_7") (pintype "bidirectional"))
    )
    (net (code "128") (name "unconnected-(U1A-PE3{slash}D11{slash}AFE1_AD10{slash}TIOA10-Pad10)") (class "Default")
      (node (ref "U1") (pin "10") (pinfunction "PE3/D11/AFE1_AD10/TIOA10_10") (pintype "bidirectional"))
    )
    (net (code "129") (name "unconnected-(U1B-HSDM-Pad136)") (class "Default")
      (node (ref "U1") (pin "136") (pinfunction "HSDM_136") (pintype "bidirectional+no_connect"))
    )
    (net (code "130") (name "unconnected-(U1B-HSDP-Pad137)") (class "Default")
      (node (ref "U1") (pin "137") (pinfunction "HSDP_137") (pintype "bidirectional+no_connect"))
    )
    (net (code "131") (name "unconnected-(U1B-VBG-Pad140)") (class "Default")
      (node (ref "U1") (pin "140") (pinfunction "VBG_140") (pintype "input+no_connect"))
    )
    (net (code "132") (name "unconnected-(Y1-EN{slash}NC-Pad1)") (class "Default")
      (node (ref "Y1") (pin "1") (pinfunction "EN/NC_1") (pintype "input+no_connect"))
    )
  )
)
